# untitled.net
KiCad netlist of a schematic drawn in EAGLE
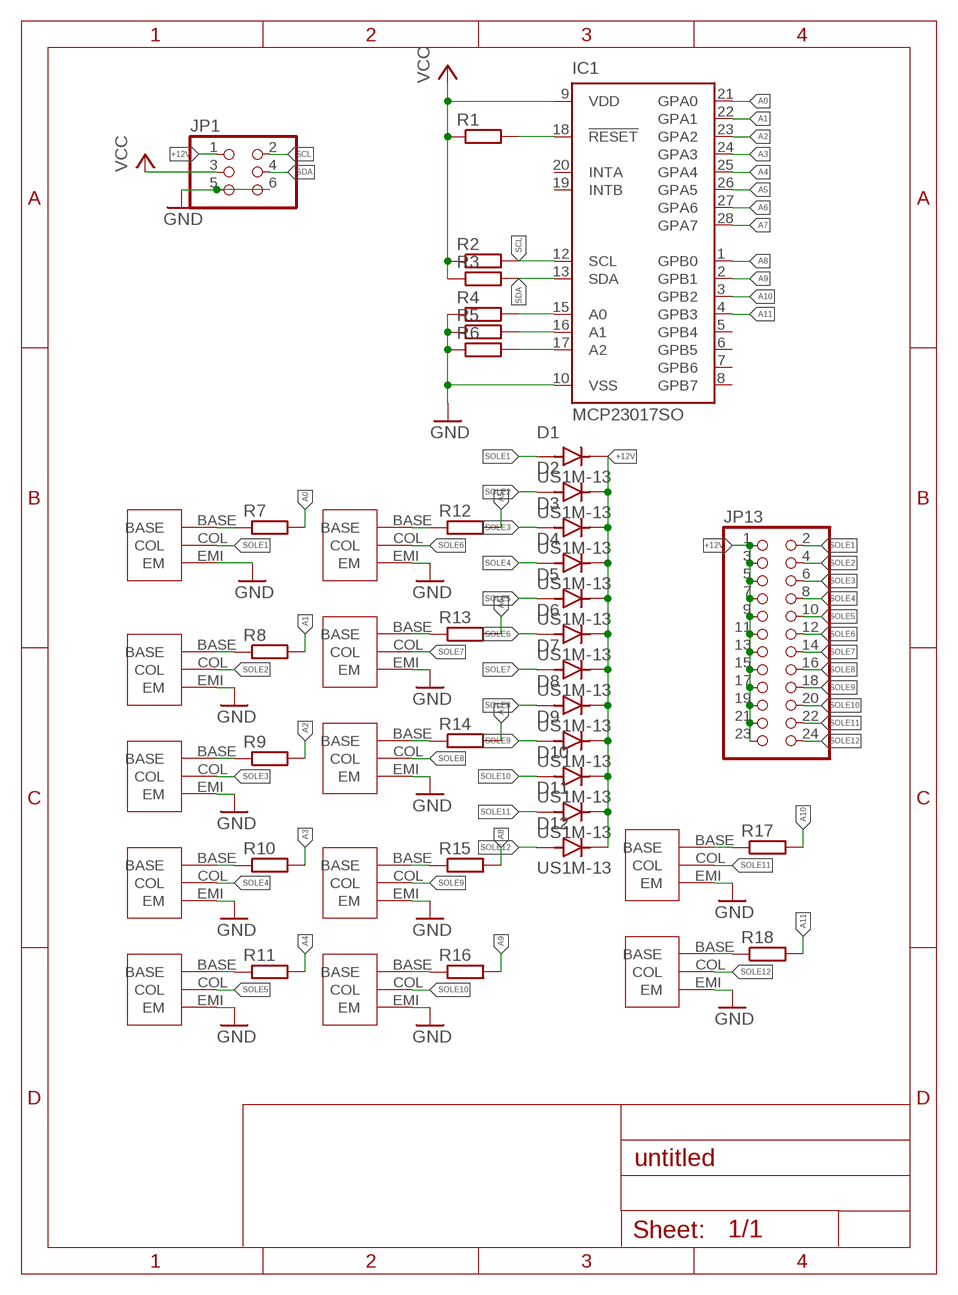
[diagram p0: schematic, sheet 1]

(export (version "E")
  (design (tool "Eeschema 10.0.6"))
  (components
    (comp (ref "BD677-SMD1")
      (value "BD677-SMD")
      (footprint "eagle-import:BD677-SMD")
      (libsource (lib "eagle-import") (part "BD677-SMD"))
    )
    (comp (ref "BD677-SMD2")
      (value "BD677-SMD")
      (footprint "eagle-import:BD677-SMD")
      (libsource (lib "eagle-import") (part "BD677-SMD"))
    )
    (comp (ref "BD677-SMD3")
      (value "BD677-SMD")
      (footprint "eagle-import:BD677-SMD")
      (libsource (lib "eagle-import") (part "BD677-SMD"))
    )
    (comp (ref "BD677-SMD4")
      (value "BD677-SMD")
      (footprint "eagle-import:BD677-SMD")
      (libsource (lib "eagle-import") (part "BD677-SMD"))
    )
    (comp (ref "BD677-SMD5")
      (value "BD677-SMD")
      (footprint "eagle-import:BD677-SMD")
      (libsource (lib "eagle-import") (part "BD677-SMD"))
    )
    (comp (ref "BD677-SMD6")
      (value "BD677-SMD")
      (footprint "eagle-import:BD677-SMD")
      (libsource (lib "eagle-import") (part "BD677-SMD"))
    )
    (comp (ref "BD677-SMD7")
      (value "BD677-SMD")
      (footprint "eagle-import:BD677-SMD")
      (libsource (lib "eagle-import") (part "BD677-SMD"))
    )
    (comp (ref "BD677-SMD8")
      (value "BD677-SMD")
      (footprint "eagle-import:BD677-SMD")
      (libsource (lib "eagle-import") (part "BD677-SMD"))
    )
    (comp (ref "BD677-SMD9")
      (value "BD677-SMD")
      (footprint "eagle-import:BD677-SMD")
      (libsource (lib "eagle-import") (part "BD677-SMD"))
    )
    (comp (ref "BD677-SMD10")
      (value "BD677-SMD")
      (footprint "eagle-import:BD677-SMD")
      (libsource (lib "eagle-import") (part "BD677-SMD"))
    )
    (comp (ref "BD677-SMD11")
      (value "BD677-SMD")
      (footprint "eagle-import:BD677-SMD")
      (libsource (lib "eagle-import") (part "BD677-SMD"))
    )
    (comp (ref "BD677-SMD12")
      (value "BD677-SMD")
      (footprint "eagle-import:BD677-SMD")
      (libsource (lib "eagle-import") (part "BD677-SMD"))
    )
    (comp (ref "D1")
      (value "US1M-13")
      (footprint "eagle-import:DIOM5226X240N")
      (fields (field (name "MF") "Diodes Incorporated"))
      (libsource (lib "eagle-import") (part "US1M-13"))
    )
    (comp (ref "D2")
      (value "US1M-13")
      (footprint "eagle-import:DIOM5226X240N")
      (fields (field (name "MF") "Diodes Incorporated"))
      (libsource (lib "eagle-import") (part "US1M-13"))
    )
    (comp (ref "D3")
      (value "US1M-13")
      (footprint "eagle-import:DIOM5226X240N")
      (fields (field (name "MF") "Diodes Incorporated"))
      (libsource (lib "eagle-import") (part "US1M-13"))
    )
    (comp (ref "D4")
      (value "US1M-13")
      (footprint "eagle-import:DIOM5226X240N")
      (fields (field (name "MF") "Diodes Incorporated"))
      (libsource (lib "eagle-import") (part "US1M-13"))
    )
    (comp (ref "D5")
      (value "US1M-13")
      (footprint "eagle-import:DIOM5226X240N")
      (fields (field (name "MF") "Diodes Incorporated"))
      (libsource (lib "eagle-import") (part "US1M-13"))
    )
    (comp (ref "D6")
      (value "US1M-13")
      (footprint "eagle-import:DIOM5226X240N")
      (fields (field (name "MF") "Diodes Incorporated"))
      (libsource (lib "eagle-import") (part "US1M-13"))
    )
    (comp (ref "D7")
      (value "US1M-13")
      (footprint "eagle-import:DIOM5226X240N")
      (fields (field (name "MF") "Diodes Incorporated"))
      (libsource (lib "eagle-import") (part "US1M-13"))
    )
    (comp (ref "D8")
      (value "US1M-13")
      (footprint "eagle-import:DIOM5226X240N")
      (fields (field (name "MF") "Diodes Incorporated"))
      (libsource (lib "eagle-import") (part "US1M-13"))
    )
    (comp (ref "D9")
      (value "US1M-13")
      (footprint "eagle-import:DIOM5226X240N")
      (fields (field (name "MF") "Diodes Incorporated"))
      (libsource (lib "eagle-import") (part "US1M-13"))
    )
    (comp (ref "D10")
      (value "US1M-13")
      (footprint "eagle-import:DIOM5226X240N")
      (fields (field (name "MF") "Diodes Incorporated"))
      (libsource (lib "eagle-import") (part "US1M-13"))
    )
    (comp (ref "D11")
      (value "US1M-13")
      (footprint "eagle-import:DIOM5226X240N")
      (fields (field (name "MF") "Diodes Incorporated"))
      (libsource (lib "eagle-import") (part "US1M-13"))
    )
    (comp (ref "D12")
      (value "US1M-13")
      (footprint "eagle-import:DIOM5226X240N")
      (fields (field (name "MF") "Diodes Incorporated"))
      (libsource (lib "eagle-import") (part "US1M-13"))
    )
    (comp (ref "IC1")
      (value "MCP23017SO")
      (footprint "eagle-import:SO28W")
      (fields (field (name "MF") "MICROCHIP") (field (name "MPN") "MCP23017-E/SO"))
      (libsource (lib "eagle-import") (part "MCP23017SO"))
    )
    (comp (ref "JP1")
      (value "PINHD-2X3")
      (footprint "eagle-import:2X03")
      (libsource (lib "eagle-import") (part "PINHD-2X3"))
    )
    (comp (ref "JP13")
      (value "PINHD-2X12")
      (footprint "eagle-import:2X12")
      (libsource (lib "eagle-import") (part "PINHD-2X12"))
    )
    (comp (ref "R1")
      (value "R-EU_R0805")
      (footprint "eagle-import:R0805")
      (libsource (lib "eagle-import") (part "R-EU_R0805"))
    )
    (comp (ref "R2")
      (value "R-EU_R0805")
      (footprint "eagle-import:R0805")
      (libsource (lib "eagle-import") (part "R-EU_R0805"))
    )
    (comp (ref "R3")
      (value "R-EU_R0805")
      (footprint "eagle-import:R0805")
      (libsource (lib "eagle-import") (part "R-EU_R0805"))
    )
    (comp (ref "R4")
      (value "R-EU_R0805")
      (footprint "eagle-import:R0805")
      (libsource (lib "eagle-import") (part "R-EU_R0805"))
    )
    (comp (ref "R5")
      (value "R-EU_R0805")
      (footprint "eagle-import:R0805")
      (libsource (lib "eagle-import") (part "R-EU_R0805"))
    )
    (comp (ref "R6")
      (value "R-EU_R0805")
      (footprint "eagle-import:R0805")
      (libsource (lib "eagle-import") (part "R-EU_R0805"))
    )
    (comp (ref "R7")
      (value "R-EU_R0805")
      (footprint "eagle-import:R0805")
      (libsource (lib "eagle-import") (part "R-EU_R0805"))
    )
    (comp (ref "R8")
      (value "R-EU_R0805")
      (footprint "eagle-import:R0805")
      (libsource (lib "eagle-import") (part "R-EU_R0805"))
    )
    (comp (ref "R9")
      (value "R-EU_R0805")
      (footprint "eagle-import:R0805")
      (libsource (lib "eagle-import") (part "R-EU_R0805"))
    )
    (comp (ref "R10")
      (value "R-EU_R0805")
      (footprint "eagle-import:R0805")
      (libsource (lib "eagle-import") (part "R-EU_R0805"))
    )
    (comp (ref "R11")
      (value "R-EU_R0805")
      (footprint "eagle-import:R0805")
      (libsource (lib "eagle-import") (part "R-EU_R0805"))
    )
    (comp (ref "R12")
      (value "R-EU_R0805")
      (footprint "eagle-import:R0805")
      (libsource (lib "eagle-import") (part "R-EU_R0805"))
    )
    (comp (ref "R13")
      (value "R-EU_R0805")
      (footprint "eagle-import:R0805")
      (libsource (lib "eagle-import") (part "R-EU_R0805"))
    )
    (comp (ref "R14")
      (value "R-EU_R0805")
      (footprint "eagle-import:R0805")
      (libsource (lib "eagle-import") (part "R-EU_R0805"))
    )
    (comp (ref "R15")
      (value "R-EU_R0805")
      (footprint "eagle-import:R0805")
      (libsource (lib "eagle-import") (part "R-EU_R0805"))
    )
    (comp (ref "R16")
      (value "R-EU_R0805")
      (footprint "eagle-import:R0805")
      (libsource (lib "eagle-import") (part "R-EU_R0805"))
    )
    (comp (ref "R17")
      (value "R-EU_R0805")
      (footprint "eagle-import:R0805")
      (libsource (lib "eagle-import") (part "R-EU_R0805"))
    )
    (comp (ref "R18")
      (value "R-EU_R0805")
      (footprint "eagle-import:R0805")
      (libsource (lib "eagle-import") (part "R-EU_R0805"))
    )
  )
  (nets
    (net (code "1") (name "+12V") (class "Default")
      (node (ref "D1") (pin "C") (pinfunction "K_C") (pintype "passive"))
      (node (ref "D10") (pin "C") (pinfunction "K_C") (pintype "passive"))
      (node (ref "D11") (pin "C") (pinfunction "K_C") (pintype "passive"))
      (node (ref "D12") (pin "C") (pinfunction "K_C") (pintype "passive"))
      (node (ref "D2") (pin "C") (pinfunction "K_C") (pintype "passive"))
      (node (ref "D3") (pin "C") (pinfunction "K_C") (pintype "passive"))
      (node (ref "D4") (pin "C") (pinfunction "K_C") (pintype "passive"))
      (node (ref "D5") (pin "C") (pinfunction "K_C") (pintype "passive"))
      (node (ref "D6") (pin "C") (pinfunction "K_C") (pintype "passive"))
      (node (ref "D7") (pin "C") (pinfunction "K_C") (pintype "passive"))
      (node (ref "D8") (pin "C") (pinfunction "K_C") (pintype "passive"))
      (node (ref "D9") (pin "C") (pinfunction "K_C") (pintype "passive"))
      (node (ref "JP1") (pin "1") (pinfunction "1_1") (pintype "passive"))
      (node (ref "JP13") (pin "1") (pinfunction "1_1") (pintype "passive"))
      (node (ref "JP13") (pin "11") (pinfunction "11_11") (pintype "passive"))
      (node (ref "JP13") (pin "13") (pinfunction "13_13") (pintype "passive"))
      (node (ref "JP13") (pin "15") (pinfunction "15_15") (pintype "passive"))
      (node (ref "JP13") (pin "17") (pinfunction "17_17") (pintype "passive"))
      (node (ref "JP13") (pin "19") (pinfunction "19_19") (pintype "passive"))
      (node (ref "JP13") (pin "21") (pinfunction "21_21") (pintype "passive"))
      (node (ref "JP13") (pin "23") (pinfunction "23_23") (pintype "passive"))
      (node (ref "JP13") (pin "3") (pinfunction "3_3") (pintype "passive"))
      (node (ref "JP13") (pin "5") (pinfunction "5_5") (pintype "passive"))
      (node (ref "JP13") (pin "7") (pinfunction "7_7") (pintype "passive"))
      (node (ref "JP13") (pin "9") (pinfunction "9_9") (pintype "passive"))
    )
    (net (code "2") (name "A0") (class "Default")
      (node (ref "IC1") (pin "21") (pinfunction "GPA0_21") (pintype "bidirectional"))
      (node (ref "R7") (pin "2") (pinfunction "2_2") (pintype "passive"))
    )
    (net (code "3") (name "A1") (class "Default")
      (node (ref "IC1") (pin "22") (pinfunction "GPA1_22") (pintype "bidirectional"))
      (node (ref "R8") (pin "2") (pinfunction "2_2") (pintype "passive"))
    )
    (net (code "4") (name "A2") (class "Default")
      (node (ref "IC1") (pin "23") (pinfunction "GPA2_23") (pintype "bidirectional"))
      (node (ref "R9") (pin "2") (pinfunction "2_2") (pintype "passive"))
    )
    (net (code "5") (name "A3") (class "Default")
      (node (ref "IC1") (pin "24") (pinfunction "GPA3_24") (pintype "bidirectional"))
      (node (ref "R10") (pin "2") (pinfunction "2_2") (pintype "passive"))
    )
    (net (code "6") (name "A4") (class "Default")
      (node (ref "IC1") (pin "25") (pinfunction "GPA4_25") (pintype "bidirectional"))
      (node (ref "R11") (pin "2") (pinfunction "2_2") (pintype "passive"))
    )
    (net (code "7") (name "A5") (class "Default")
      (node (ref "IC1") (pin "26") (pinfunction "GPA5_26") (pintype "bidirectional"))
      (node (ref "R12") (pin "2") (pinfunction "2_2") (pintype "passive"))
    )
    (net (code "8") (name "A6") (class "Default")
      (node (ref "IC1") (pin "27") (pinfunction "GPA6_27") (pintype "bidirectional"))
      (node (ref "R13") (pin "2") (pinfunction "2_2") (pintype "passive"))
    )
    (net (code "9") (name "A7") (class "Default")
      (node (ref "IC1") (pin "28") (pinfunction "GPA7_28") (pintype "bidirectional"))
      (node (ref "R14") (pin "2") (pinfunction "2_2") (pintype "passive"))
    )
    (net (code "10") (name "A8") (class "Default")
      (node (ref "IC1") (pin "1") (pinfunction "GPB0_1") (pintype "bidirectional"))
      (node (ref "R15") (pin "2") (pinfunction "2_2") (pintype "passive"))
    )
    (net (code "11") (name "A9") (class "Default")
      (node (ref "IC1") (pin "2") (pinfunction "GPB1_2") (pintype "bidirectional"))
      (node (ref "R16") (pin "2") (pinfunction "2_2") (pintype "passive"))
    )
    (net (code "12") (name "A10") (class "Default")
      (node (ref "IC1") (pin "3") (pinfunction "GPB2_3") (pintype "bidirectional"))
      (node (ref "R17") (pin "2") (pinfunction "2_2") (pintype "passive"))
    )
    (net (code "13") (name "A11") (class "Default")
      (node (ref "IC1") (pin "4") (pinfunction "GPB3_4") (pintype "bidirectional"))
      (node (ref "R18") (pin "2") (pinfunction "2_2") (pintype "passive"))
    )
    (net (code "14") (name "GND") (class "Default")
      (node (ref "BD677-SMD1") (pin "EMI") (pinfunction "EM_EMI") (pintype "bidirectional"))
      (node (ref "BD677-SMD10") (pin "EMI") (pinfunction "EM_EMI") (pintype "bidirectional"))
      (node (ref "BD677-SMD11") (pin "EMI") (pinfunction "EM_EMI") (pintype "bidirectional"))
      (node (ref "BD677-SMD12") (pin "EMI") (pinfunction "EM_EMI") (pintype "bidirectional"))
      (node (ref "BD677-SMD2") (pin "EMI") (pinfunction "EM_EMI") (pintype "bidirectional"))
      (node (ref "BD677-SMD3") (pin "EMI") (pinfunction "EM_EMI") (pintype "bidirectional"))
      (node (ref "BD677-SMD4") (pin "EMI") (pinfunction "EM_EMI") (pintype "bidirectional"))
      (node (ref "BD677-SMD5") (pin "EMI") (pinfunction "EM_EMI") (pintype "bidirectional"))
      (node (ref "BD677-SMD6") (pin "EMI") (pinfunction "EM_EMI") (pintype "bidirectional"))
      (node (ref "BD677-SMD7") (pin "EMI") (pinfunction "EM_EMI") (pintype "bidirectional"))
      (node (ref "BD677-SMD8") (pin "EMI") (pinfunction "EM_EMI") (pintype "bidirectional"))
      (node (ref "BD677-SMD9") (pin "EMI") (pinfunction "EM_EMI") (pintype "bidirectional"))
      (node (ref "IC1") (pin "10") (pinfunction "VSS_10") (pintype "power_in"))
      (node (ref "JP1") (pin "5") (pinfunction "5_5") (pintype "passive"))
      (node (ref "JP1") (pin "6") (pinfunction "6_6") (pintype "passive"))
      (node (ref "R4") (pin "1") (pinfunction "1_1") (pintype "passive"))
      (node (ref "R5") (pin "1") (pinfunction "1_1") (pintype "passive"))
      (node (ref "R6") (pin "1") (pinfunction "1_1") (pintype "passive"))
    )
    (net (code "15") (name "Net-(BD677-SMD1-PadBASE)") (class "Default")
      (node (ref "BD677-SMD1") (pin "BASE") (pinfunction "BASE_BASE") (pintype "bidirectional"))
      (node (ref "R7") (pin "1") (pinfunction "1_1") (pintype "passive"))
    )
    (net (code "16") (name "Net-(BD677-SMD2-PadBASE)") (class "Default")
      (node (ref "BD677-SMD2") (pin "BASE") (pinfunction "BASE_BASE") (pintype "bidirectional"))
      (node (ref "R8") (pin "1") (pinfunction "1_1") (pintype "passive"))
    )
    (net (code "17") (name "Net-(BD677-SMD3-PadBASE)") (class "Default")
      (node (ref "BD677-SMD3") (pin "BASE") (pinfunction "BASE_BASE") (pintype "bidirectional"))
      (node (ref "R9") (pin "1") (pinfunction "1_1") (pintype "passive"))
    )
    (net (code "18") (name "Net-(BD677-SMD4-PadBASE)") (class "Default")
      (node (ref "BD677-SMD4") (pin "BASE") (pinfunction "BASE_BASE") (pintype "bidirectional"))
      (node (ref "R10") (pin "1") (pinfunction "1_1") (pintype "passive"))
    )
    (net (code "19") (name "Net-(BD677-SMD5-PadBASE)") (class "Default")
      (node (ref "BD677-SMD5") (pin "BASE") (pinfunction "BASE_BASE") (pintype "bidirectional"))
      (node (ref "R11") (pin "1") (pinfunction "1_1") (pintype "passive"))
    )
    (net (code "20") (name "Net-(BD677-SMD6-PadBASE)") (class "Default")
      (node (ref "BD677-SMD6") (pin "BASE") (pinfunction "BASE_BASE") (pintype "bidirectional"))
      (node (ref "R12") (pin "1") (pinfunction "1_1") (pintype "passive"))
    )
    (net (code "21") (name "Net-(BD677-SMD7-PadBASE)") (class "Default")
      (node (ref "BD677-SMD7") (pin "BASE") (pinfunction "BASE_BASE") (pintype "bidirectional"))
      (node (ref "R13") (pin "1") (pinfunction "1_1") (pintype "passive"))
    )
    (net (code "22") (name "Net-(BD677-SMD8-PadBASE)") (class "Default")
      (node (ref "BD677-SMD8") (pin "BASE") (pinfunction "BASE_BASE") (pintype "bidirectional"))
      (node (ref "R14") (pin "1") (pinfunction "1_1") (pintype "passive"))
    )
    (net (code "23") (name "Net-(BD677-SMD9-PadBASE)") (class "Default")
      (node (ref "BD677-SMD9") (pin "BASE") (pinfunction "BASE_BASE") (pintype "bidirectional"))
      (node (ref "R15") (pin "1") (pinfunction "1_1") (pintype "passive"))
    )
    (net (code "24") (name "Net-(BD677-SMD10-PadBASE)") (class "Default")
      (node (ref "BD677-SMD10") (pin "BASE") (pinfunction "BASE_BASE") (pintype "bidirectional"))
      (node (ref "R16") (pin "1") (pinfunction "1_1") (pintype "passive"))
    )
    (net (code "25") (name "Net-(BD677-SMD11-PadBASE)") (class "Default")
      (node (ref "BD677-SMD11") (pin "BASE") (pinfunction "BASE_BASE") (pintype "bidirectional"))
      (node (ref "R17") (pin "1") (pinfunction "1_1") (pintype "passive"))
    )
    (net (code "26") (name "Net-(BD677-SMD12-PadBASE)") (class "Default")
      (node (ref "BD677-SMD12") (pin "BASE") (pinfunction "BASE_BASE") (pintype "bidirectional"))
      (node (ref "R18") (pin "1") (pinfunction "1_1") (pintype "passive"))
    )
    (net (code "27") (name "Net-(IC1-A0)") (class "Default")
      (node (ref "IC1") (pin "15") (pinfunction "A0_15") (pintype "input"))
      (node (ref "R4") (pin "2") (pinfunction "2_2") (pintype "passive"))
    )
    (net (code "28") (name "Net-(IC1-A1)") (class "Default")
      (node (ref "IC1") (pin "16") (pinfunction "A1_16") (pintype "input"))
      (node (ref "R5") (pin "2") (pinfunction "2_2") (pintype "passive"))
    )
    (net (code "29") (name "Net-(IC1-A2)") (class "Default")
      (node (ref "IC1") (pin "17") (pinfunction "A2_17") (pintype "input"))
      (node (ref "R6") (pin "2") (pinfunction "2_2") (pintype "passive"))
    )
    (net (code "30") (name "Net-(IC1-~{RESET})") (class "Default")
      (node (ref "IC1") (pin "18") (pinfunction "~{RESET}_18") (pintype "input"))
      (node (ref "R1") (pin "2") (pinfunction "2_2") (pintype "passive"))
    )
    (net (code "31") (name "SCL") (class "Default")
      (node (ref "IC1") (pin "12") (pinfunction "SCL_12") (pintype "input"))
      (node (ref "JP1") (pin "2") (pinfunction "2_2") (pintype "passive"))
      (node (ref "R2") (pin "2") (pinfunction "2_2") (pintype "passive"))
    )
    (net (code "32") (name "SDA") (class "Default")
      (node (ref "IC1") (pin "13") (pinfunction "SDA_13") (pintype "bidirectional"))
      (node (ref "JP1") (pin "4") (pinfunction "4_4") (pintype "passive"))
      (node (ref "R3") (pin "2") (pinfunction "2_2") (pintype "passive"))
    )
    (net (code "33") (name "SOLE1") (class "Default")
      (node (ref "BD677-SMD1") (pin "COL") (pinfunction "COL_COL") (pintype "bidirectional"))
      (node (ref "D1") (pin "A") (pinfunction "A_A") (pintype "passive"))
      (node (ref "JP13") (pin "2") (pinfunction "2_2") (pintype "passive"))
    )
    (net (code "34") (name "SOLE2") (class "Default")
      (node (ref "BD677-SMD2") (pin "COL") (pinfunction "COL_COL") (pintype "bidirectional"))
      (node (ref "D2") (pin "A") (pinfunction "A_A") (pintype "passive"))
      (node (ref "JP13") (pin "4") (pinfunction "4_4") (pintype "passive"))
    )
    (net (code "35") (name "SOLE3") (class "Default")
      (node (ref "BD677-SMD3") (pin "COL") (pinfunction "COL_COL") (pintype "bidirectional"))
      (node (ref "D3") (pin "A") (pinfunction "A_A") (pintype "passive"))
      (node (ref "JP13") (pin "6") (pinfunction "6_6") (pintype "passive"))
    )
    (net (code "36") (name "SOLE4") (class "Default")
      (node (ref "BD677-SMD4") (pin "COL") (pinfunction "COL_COL") (pintype "bidirectional"))
      (node (ref "D4") (pin "A") (pinfunction "A_A") (pintype "passive"))
      (node (ref "JP13") (pin "8") (pinfunction "8_8") (pintype "passive"))
    )
    (net (code "37") (name "SOLE5") (class "Default")
      (node (ref "BD677-SMD5") (pin "COL") (pinfunction "COL_COL") (pintype "bidirectional"))
      (node (ref "D5") (pin "A") (pinfunction "A_A") (pintype "passive"))
      (node (ref "JP13") (pin "10") (pinfunction "10_10") (pintype "passive"))
    )
    (net (code "38") (name "SOLE6") (class "Default")
      (node (ref "BD677-SMD6") (pin "COL") (pinfunction "COL_COL") (pintype "bidirectional"))
      (node (ref "D6") (pin "A") (pinfunction "A_A") (pintype "passive"))
      (node (ref "JP13") (pin "12") (pinfunction "12_12") (pintype "passive"))
    )
    (net (code "39") (name "SOLE7") (class "Default")
      (node (ref "BD677-SMD7") (pin "COL") (pinfunction "COL_COL") (pintype "bidirectional"))
      (node (ref "D7") (pin "A") (pinfunction "A_A") (pintype "passive"))
      (node (ref "JP13") (pin "14") (pinfunction "14_14") (pintype "passive"))
    )
    (net (code "40") (name "SOLE8") (class "Default")
      (node (ref "BD677-SMD8") (pin "COL") (pinfunction "COL_COL") (pintype "bidirectional"))
      (node (ref "D8") (pin "A") (pinfunction "A_A") (pintype "passive"))
      (node (ref "JP13") (pin "16") (pinfunction "16_16") (pintype "passive"))
    )
    (net (code "41") (name "SOLE9") (class "Default")
      (node (ref "BD677-SMD9") (pin "COL") (pinfunction "COL_COL") (pintype "bidirectional"))
      (node (ref "D9") (pin "A") (pinfunction "A_A") (pintype "passive"))
      (node (ref "JP13") (pin "18") (pinfunction "18_18") (pintype "passive"))
    )
    (net (code "42") (name "SOLE10") (class "Default")
      (node (ref "BD677-SMD10") (pin "COL") (pinfunction "COL_COL") (pintype "bidirectional"))
      (node (ref "D10") (pin "A") (pinfunction "A_A") (pintype "passive"))
      (node (ref "JP13") (pin "20") (pinfunction "20_20") (pintype "passive"))
    )
    (net (code "43") (name "SOLE11") (class "Default")
      (node (ref "BD677-SMD11") (pin "COL") (pinfunction "COL_COL") (pintype "bidirectional"))
      (node (ref "D11") (pin "A") (pinfunction "A_A") (pintype "passive"))
      (node (ref "JP13") (pin "22") (pinfunction "22_22") (pintype "passive"))
    )
    (net (code "44") (name "SOLE12") (class "Default")
      (node (ref "BD677-SMD12") (pin "COL") (pinfunction "COL_COL") (pintype "bidirectional"))
      (node (ref "D12") (pin "A") (pinfunction "A_A") (pintype "passive"))
      (node (ref "JP13") (pin "24") (pinfunction "24_24") (pintype "passive"))
    )
    (net (code "45") (name "VCC") (class "Default")
      (node (ref "IC1") (pin "9") (pinfunction "VDD_9") (pintype "power_in"))
      (node (ref "JP1") (pin "3") (pinfunction "3_3") (pintype "passive"))
      (node (ref "R1") (pin "1") (pinfunction "1_1") (pintype "passive"))
      (node (ref "R2") (pin "1") (pinfunction "1_1") (pintype "passive"))
      (node (ref "R3") (pin "1") (pinfunction "1_1") (pintype "passive"))
    )
    (net (code "46") (name "unconnected-(IC1-GPB4-Pad5)") (class "Default")
      (node (ref "IC1") (pin "5") (pinfunction "GPB4_5") (pintype "bidirectional"))
    )
    (net (code "47") (name "unconnected-(IC1-GPB5-Pad6)") (class "Default")
      (node (ref "IC1") (pin "6") (pinfunction "GPB5_6") (pintype "bidirectional"))
    )
    (net (code "48") (name "unconnected-(IC1-GPB6-Pad7)") (class "Default")
      (node (ref "IC1") (pin "7") (pinfunction "GPB6_7") (pintype "bidirectional"))
    )
    (net (code "49") (name "unconnected-(IC1-GPB7-Pad8)") (class "Default")
      (node (ref "IC1") (pin "8") (pinfunction "GPB7_8") (pintype "bidirectional"))
    )
    (net (code "50") (name "unconnected-(IC1-INTA-Pad20)") (class "Default")
      (node (ref "IC1") (pin "20") (pinfunction "INTA_20") (pintype "output"))
    )
    (net (code "51") (name "unconnected-(IC1-INTB-Pad19)") (class "Default")
      (node (ref "IC1") (pin "19") (pinfunction "INTB_19") (pintype "output"))
    )
  )
)
